# Deneigus_Servo.net
KiCad netlist of a schematic drawn in Altium Designer
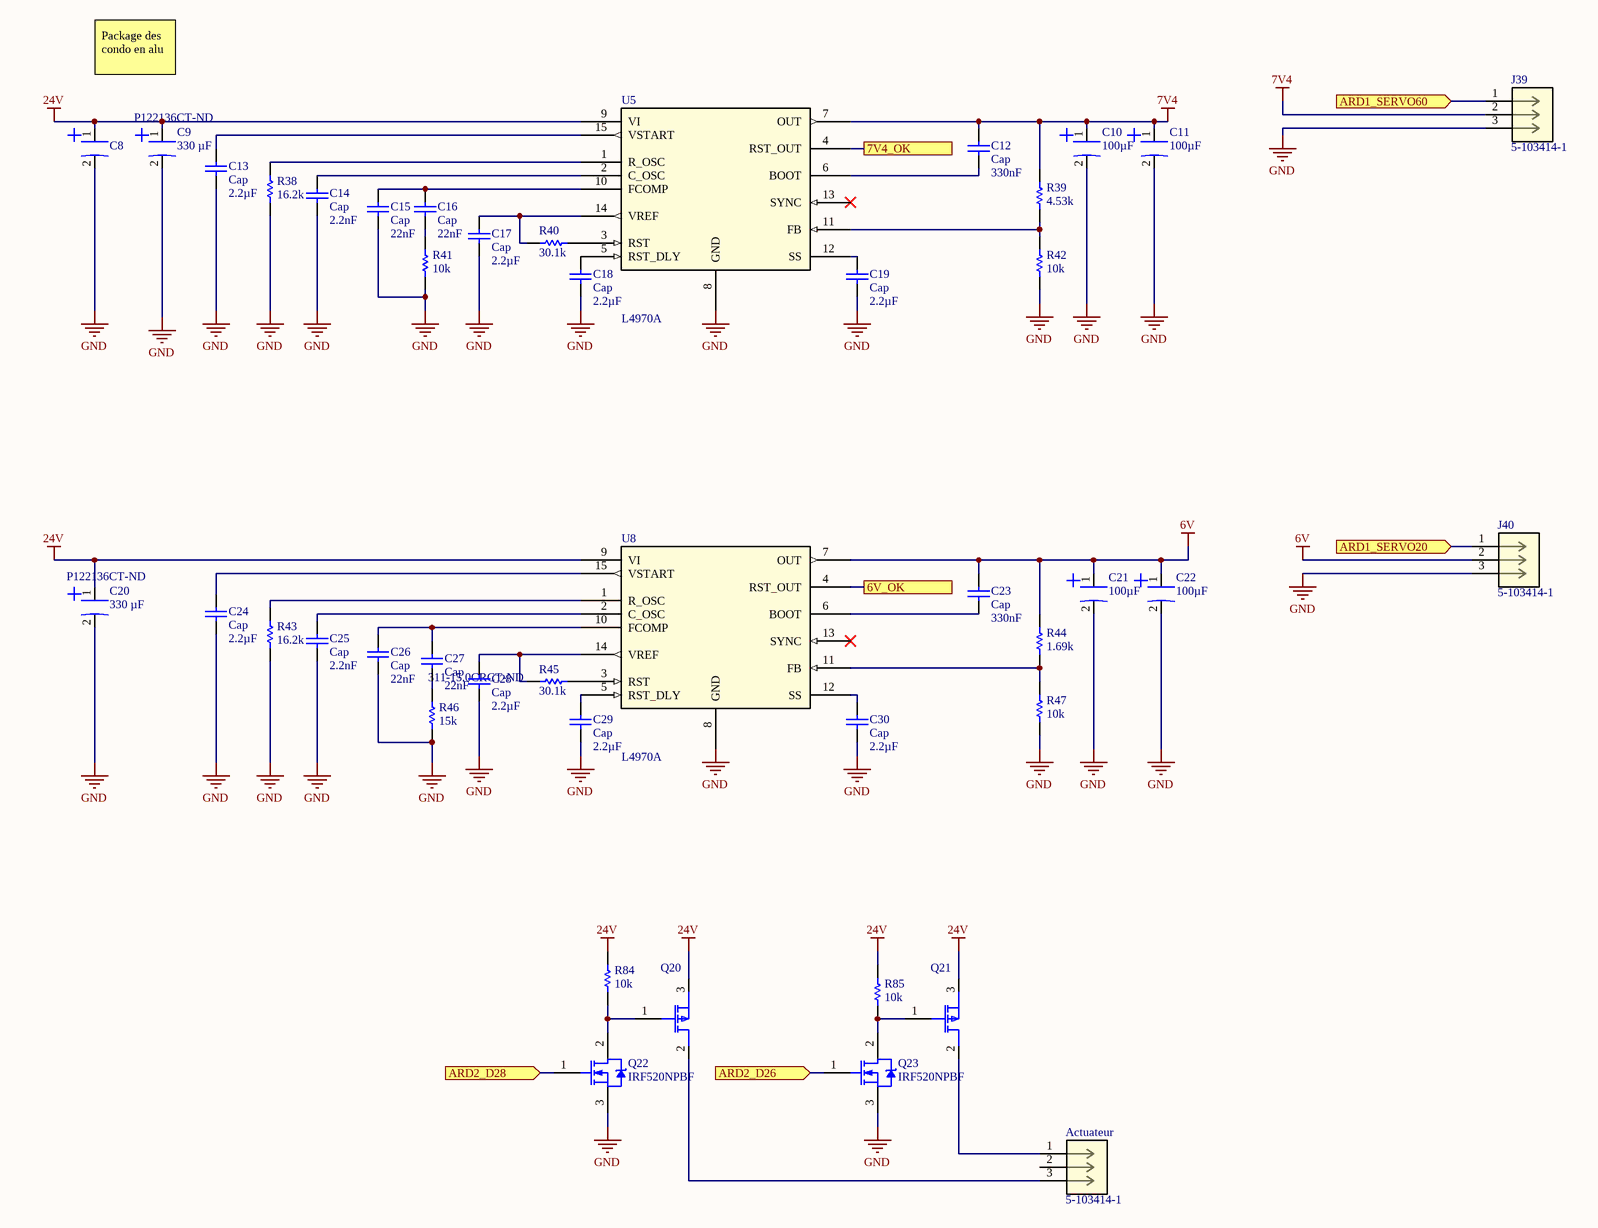
[diagram p0: Deneigus_Servo.SchDoc]

(export (version "E")
  (design (tool "Eeschema 10.0.6"))
  (components
    (comp (ref "Actuateur")
      (value "5-103414-1")
      (footprint "2021-04-13_19-21-58:CONN_5-103414-1_TYCO")
      (description "No Description Available")
      (fields (field (name "COPYRIGHT") "Copyright (C) 2016 Accelerated Designs. All rights reserved"))
      (libsource (lib "3pins") (part "5-103414-1"))
    )
    (comp (ref "C8")
      (value "CAP ALUM 3300UF 20% 50V SNAP")
      (footprint "3300 uF 50V Cap")
      (fields (field (name "VOLTAGE") "50V") (field (name "TOLERANCE") "20%"))
      (libsource (lib "S7CAS-APP1") (part "3300 µF 50V"))
    )
    (comp (ref "C9")
      (value "330 µF")
      (footprint "330uF (10.3x10.3mm)")
      (fields
        (field (name "MFG") "Würth Elektronik")
        (field (name "MFG PART NUMBER") "875105344006")
        (field (name "SUPPLIER PART NUMBER 1") "P122136CT-ND")
        (field (name "Comment") "CAP ALUM POLY 47UF 20% 16V SMD")
      )
      (libsource (lib "S7CAS-APP1") (part "47µF SMD"))
    )
    (comp (ref "C10")
      (value "100µF")
      (footprint "47uF")
      (fields
        (field (name "MFG") "Würth Elektronik")
        (field (name "MFG PART NUMBER") "875105344010")
        (field (name "Comment") "CAP ALUM POLY 47UF 20% 16V SMD")
      )
      (libsource (lib "S7CAS-APP1") (part "47µF SMD"))
    )
    (comp (ref "C11")
      (value "100µF")
      (footprint "47uF")
      (fields
        (field (name "MFG") "Würth Elektronik")
        (field (name "MFG PART NUMBER") "875105344010")
        (field (name "Comment") "CAP ALUM POLY 47UF 20% 16V SMD")
      )
      (libsource (lib "S7CAS-APP1") (part "47µF SMD"))
    )
    (comp (ref "C12")
      (value "Cap")
      (footprint "CAP_0805")
      (description "Capacitor")
      (fields (field (name "ALTIUM_VALUE") "330nF") (field (name "PUBLISHER") "Altium Limited"))
      (libsource (lib "Miscellaneous Devices") (part "Cap"))
    )
    (comp (ref "C13")
      (value "Cap")
      (footprint "CAP_0805")
      (description "Capacitor")
      (fields (field (name "ALTIUM_VALUE") "2.2µF") (field (name "PUBLISHER") "Altium Limited"))
      (libsource (lib "Miscellaneous Devices") (part "Cap"))
    )
    (comp (ref "C14")
      (value "Cap")
      (footprint "CAP_0805")
      (description "Capacitor")
      (fields (field (name "ALTIUM_VALUE") "2.2nF") (field (name "PUBLISHER") "Altium Limited"))
      (libsource (lib "Miscellaneous Devices") (part "Cap"))
    )
    (comp (ref "C15")
      (value "Cap")
      (footprint "RAD-0.3")
      (description "Capacitor")
      (fields (field (name "ALTIUM_VALUE") "22nF") (field (name "PUBLISHER") "Altium Limited"))
      (libsource (lib "Miscellaneous Devices") (part "Cap"))
    )
    (comp (ref "C16")
      (value "Cap")
      (footprint "RAD-0.3")
      (description "Capacitor")
      (fields (field (name "ALTIUM_VALUE") "22nF") (field (name "PUBLISHER") "Altium Limited"))
      (libsource (lib "Miscellaneous Devices") (part "Cap"))
    )
    (comp (ref "C17")
      (value "Cap")
      (footprint "CAP_0805")
      (description "Capacitor")
      (fields (field (name "ALTIUM_VALUE") "2.2µF") (field (name "PUBLISHER") "Altium Limited"))
      (libsource (lib "Miscellaneous Devices") (part "Cap"))
    )
    (comp (ref "C18")
      (value "Cap")
      (footprint "CAP_0805")
      (description "Capacitor")
      (fields (field (name "ALTIUM_VALUE") "2.2µF") (field (name "PUBLISHER") "Altium Limited"))
      (libsource (lib "Miscellaneous Devices") (part "Cap"))
    )
    (comp (ref "C19")
      (value "Cap")
      (footprint "CAP_0805")
      (description "Capacitor")
      (fields (field (name "ALTIUM_VALUE") "2.2µF") (field (name "PUBLISHER") "Altium Limited"))
      (libsource (lib "Miscellaneous Devices") (part "Cap"))
    )
    (comp (ref "C20")
      (value "330 µF")
      (footprint "330uF (10.3x10.3mm)")
      (fields
        (field (name "MFG") "Würth Elektronik")
        (field (name "MFG PART NUMBER") "875105344006")
        (field (name "SUPPLIER PART NUMBER 1") "P122136CT-ND")
        (field (name "Comment") "CAP ALUM POLY 47UF 20% 16V SMD")
      )
      (libsource (lib "S7CAS-APP1") (part "47µF SMD"))
    )
    (comp (ref "C21")
      (value "100µF")
      (footprint "47uF")
      (fields
        (field (name "MFG") "Würth Elektronik")
        (field (name "MFG PART NUMBER") "875105344010")
        (field (name "Comment") "CAP ALUM POLY 47UF 20% 16V SMD")
      )
      (libsource (lib "S7CAS-APP1") (part "47µF SMD"))
    )
    (comp (ref "C22")
      (value "100µF")
      (footprint "47uF")
      (fields
        (field (name "MFG") "Würth Elektronik")
        (field (name "MFG PART NUMBER") "875105344010")
        (field (name "Comment") "CAP ALUM POLY 47UF 20% 16V SMD")
      )
      (libsource (lib "S7CAS-APP1") (part "47µF SMD"))
    )
    (comp (ref "C23")
      (value "Cap")
      (footprint "CAP_0805")
      (description "Capacitor")
      (fields (field (name "ALTIUM_VALUE") "330nF") (field (name "PUBLISHER") "Altium Limited"))
      (libsource (lib "Miscellaneous Devices") (part "Cap"))
    )
    (comp (ref "C24")
      (value "Cap")
      (footprint "CAP_0805")
      (description "Capacitor")
      (fields (field (name "ALTIUM_VALUE") "2.2µF") (field (name "PUBLISHER") "Altium Limited"))
      (libsource (lib "Miscellaneous Devices") (part "Cap"))
    )
    (comp (ref "C25")
      (value "Cap")
      (footprint "CAP_0805")
      (description "Capacitor")
      (fields (field (name "ALTIUM_VALUE") "2.2nF") (field (name "PUBLISHER") "Altium Limited"))
      (libsource (lib "Miscellaneous Devices") (part "Cap"))
    )
    (comp (ref "C26")
      (value "Cap")
      (footprint "RAD-0.3")
      (description "Capacitor")
      (fields (field (name "ALTIUM_VALUE") "22nF") (field (name "PUBLISHER") "Altium Limited"))
      (libsource (lib "Miscellaneous Devices") (part "Cap"))
    )
    (comp (ref "C27")
      (value "Cap")
      (footprint "RAD-0.3")
      (description "Capacitor")
      (fields (field (name "ALTIUM_VALUE") "22nF") (field (name "PUBLISHER") "Altium Limited"))
      (libsource (lib "Miscellaneous Devices") (part "Cap"))
    )
    (comp (ref "C28")
      (value "Cap")
      (footprint "CAP_0805")
      (description "Capacitor")
      (fields (field (name "ALTIUM_VALUE") "2.2µF") (field (name "PUBLISHER") "Altium Limited"))
      (libsource (lib "Miscellaneous Devices") (part "Cap"))
    )
    (comp (ref "C29")
      (value "Cap")
      (footprint "CAP_0805")
      (description "Capacitor")
      (fields (field (name "ALTIUM_VALUE") "2.2µF") (field (name "PUBLISHER") "Altium Limited"))
      (libsource (lib "Miscellaneous Devices") (part "Cap"))
    )
    (comp (ref "C30")
      (value "Cap")
      (footprint "CAP_0805")
      (description "Capacitor")
      (fields (field (name "ALTIUM_VALUE") "2.2µF") (field (name "PUBLISHER") "Altium Limited"))
      (libsource (lib "Miscellaneous Devices") (part "Cap"))
    )
    (comp (ref "J39")
      (value "5-103414-1")
      (footprint "2021-04-13_19-21-58:CONN_5-103414-1_TYCO")
      (description "No Description Available")
      (fields (field (name "COPYRIGHT") "Copyright (C) 2016 Accelerated Designs. All rights reserved"))
      (libsource (lib "3pins") (part "5-103414-1"))
    )
    (comp (ref "J40")
      (value "5-103414-1")
      (footprint "2021-04-13_19-21-58:CONN_5-103414-1_TYCO")
      (description "No Description Available")
      (fields (field (name "COPYRIGHT") "Copyright (C) 2016 Accelerated Designs. All rights reserved"))
      (libsource (lib "3pins") (part "5-103414-1"))
    )
    (comp (ref "Q20")
      (value "MOSFET P-CH 55V 12A TO220AB")
      (footprint "IRF9Z24NPBF")
      (libsource (lib "S7CAS-APP1") (part "IRF9Z24NPBF"))
    )
    (comp (ref "Q21")
      (value "MOSFET P-CH 55V 12A TO220AB")
      (footprint "IRF9Z24NPBF")
      (libsource (lib "S7CAS-APP1") (part "IRF9Z24NPBF"))
    )
    (comp (ref "Q22")
      (value "IRF520NPBF")
      (footprint "INTR-TO-220AB-3")
      (description "HEXFET(R) Power MOSFET, 100 V, 9.7 A, 0.2 Ohm, -55 to 175 degC, 3-Pin FM (TO-220AB), RoHS, Tube")
      (fields (field (name "POWER") "48W") (field (name "MANUFACTURER") "International Rectifier"))
      (libsource (lib "Université de Sherbrooke") (part "NEMOS-GDS-3_B"))
    )
    (comp (ref "Q23")
      (value "IRF520NPBF")
      (footprint "INTR-TO-220AB-3")
      (description "HEXFET(R) Power MOSFET, 100 V, 9.7 A, 0.2 Ohm, -55 to 175 degC, 3-Pin FM (TO-220AB), RoHS, Tube")
      (fields (field (name "POWER") "48W") (field (name "MANUFACTURER") "International Rectifier"))
      (libsource (lib "Université de Sherbrooke") (part "NEMOS-GDS-3_B"))
    )
    (comp (ref "R38")
      (value "16.2k")
      (footprint "RES_0805")
      (description "Resistor")
      (fields (field (name "Comment") "Res1") (field (name "PUBLISHER") "Altium Limited"))
      (libsource (lib "Miscellaneous Devices") (part "Res1"))
    )
    (comp (ref "R39")
      (value "4.53k")
      (footprint "RES_0805")
      (description "Resistor")
      (fields (field (name "Comment") "Res1") (field (name "PUBLISHER") "Altium Limited"))
      (libsource (lib "Miscellaneous Devices") (part "Res1"))
    )
    (comp (ref "R40")
      (value "30.1k")
      (footprint "RES_0805")
      (description "Resistor")
      (fields (field (name "Comment") "Res1") (field (name "PUBLISHER") "Altium Limited"))
      (libsource (lib "Miscellaneous Devices") (part "Res1"))
    )
    (comp (ref "R41")
      (value "10k")
      (footprint "RES_0805")
      (description "Resistor")
      (fields (field (name "Comment") "Res1") (field (name "PUBLISHER") "Altium Limited"))
      (libsource (lib "Miscellaneous Devices") (part "Res1"))
    )
    (comp (ref "R42")
      (value "10k")
      (footprint "RES_0805")
      (description "Resistor")
      (fields (field (name "Comment") "Res1") (field (name "PUBLISHER") "Altium Limited"))
      (libsource (lib "Miscellaneous Devices") (part "Res1"))
    )
    (comp (ref "R43")
      (value "16.2k")
      (footprint "RES_0805")
      (description "Resistor")
      (fields (field (name "Comment") "Res1") (field (name "PUBLISHER") "Altium Limited"))
      (libsource (lib "Miscellaneous Devices") (part "Res1"))
    )
    (comp (ref "R44")
      (value "1.69k")
      (footprint "RES_0805")
      (description "Resistor")
      (fields (field (name "Comment") "Res1") (field (name "PUBLISHER") "Altium Limited"))
      (libsource (lib "Miscellaneous Devices") (part "Res1"))
    )
    (comp (ref "R45")
      (value "30.1k")
      (footprint "RES_0805")
      (description "Resistor")
      (fields (field (name "Comment") "Res1") (field (name "PUBLISHER") "Altium Limited"))
      (libsource (lib "Miscellaneous Devices") (part "Res1"))
    )
    (comp (ref "R46")
      (value "15k")
      (footprint "RES_0805")
      (description "Resistor")
      (fields
        (field (name "SUPPLIER PART NUMBER 1") "311-15.0CRCT-ND")
        (field (name "Comment") "Res1")
        (field (name "PUBLISHER") "Altium Limited")
      )
      (libsource (lib "Miscellaneous Devices") (part "Res1"))
    )
    (comp (ref "R47")
      (value "10k")
      (footprint "RES_0805")
      (description "Resistor")
      (fields (field (name "Comment") "Res1") (field (name "PUBLISHER") "Altium Limited"))
      (libsource (lib "Miscellaneous Devices") (part "Res1"))
    )
    (comp (ref "R84")
      (value "10k")
      (footprint "RES_0805")
      (description "Resistor")
      (fields (field (name "Comment") "Res1") (field (name "PUBLISHER") "Altium Limited"))
      (libsource (lib "Miscellaneous Devices") (part "Res1"))
    )
    (comp (ref "R85")
      (value "10k")
      (footprint "RES_0805")
      (description "Resistor")
      (fields (field (name "Comment") "Res1") (field (name "PUBLISHER") "Altium Limited"))
      (libsource (lib "Miscellaneous Devices") (part "Res1"))
    )
    (comp (ref "U5")
      (value "L4970A")
      (footprint "Multiwatt15_V_STM")
      (description "No Description Available")
      (fields (field (name "COPYRIGHT") "Copyright (C) 2018 Accelerated Designs. All rights reserved"))
      (libsource (lib "DCDC24_6") (part "L4970A"))
    )
    (comp (ref "U8")
      (value "L4970A")
      (footprint "Multiwatt15_V_STM")
      (description "No Description Available")
      (fields (field (name "COPYRIGHT") "Copyright (C) 2018 Accelerated Designs. All rights reserved"))
      (libsource (lib "DCDC24_6") (part "L4970A"))
    )
  )
  (nets
    (net (code "1") (name "/6V_OK") (class "Default")
      (node (ref "U8") (pin "4") (pinfunction "RST_OUT_4") (pintype "passive"))
    )
    (net (code "2") (name "/7V4_OK") (class "Default")
      (node (ref "U5") (pin "4") (pinfunction "RST_OUT_4") (pintype "passive"))
    )
    (net (code "3") (name "/ARD1_SERVO20") (class "Default")
      (node (ref "J40") (pin "1") (pinfunction "1_1") (pintype "passive"))
    )
    (net (code "4") (name "/ARD1_SERVO60") (class "Default")
      (node (ref "J39") (pin "1") (pinfunction "1_1") (pintype "passive"))
    )
    (net (code "5") (name "/ARD2_D26") (class "Default")
      (node (ref "Q23") (pin "1") (pinfunction "G_1") (pintype "passive"))
    )
    (net (code "6") (name "/ARD2_D28") (class "Default")
      (node (ref "Q22") (pin "1") (pinfunction "G_1") (pintype "passive"))
    )
    (net (code "7") (name "6V") (class "Default")
      (node (ref "C21") (pin "1") (pinfunction "1_1") (pintype "passive"))
      (node (ref "C22") (pin "1") (pinfunction "1_1") (pintype "passive"))
      (node (ref "C23") (pin "2") (pinfunction "2_2") (pintype "passive"))
      (node (ref "J40") (pin "2") (pinfunction "2_2") (pintype "passive"))
      (node (ref "R44") (pin "1") (pinfunction "1_1") (pintype "passive"))
      (node (ref "U8") (pin "7") (pinfunction "OUT_7") (pintype "output"))
    )
    (net (code "8") (name "7V4") (class "Default")
      (node (ref "C10") (pin "1") (pinfunction "1_1") (pintype "passive"))
      (node (ref "C11") (pin "1") (pinfunction "1_1") (pintype "passive"))
      (node (ref "C12") (pin "2") (pinfunction "2_2") (pintype "passive"))
      (node (ref "J39") (pin "2") (pinfunction "2_2") (pintype "passive"))
      (node (ref "R39") (pin "1") (pinfunction "1_1") (pintype "passive"))
      (node (ref "U5") (pin "7") (pinfunction "OUT_7") (pintype "output"))
    )
    (net (code "9") (name "24V") (class "Default")
      (node (ref "C20") (pin "1") (pinfunction "1_1") (pintype "passive"))
      (node (ref "C8") (pin "1") (pinfunction "1_1") (pintype "passive"))
      (node (ref "C9") (pin "1") (pinfunction "1_1") (pintype "passive"))
      (node (ref "Q20") (pin "3") (pinfunction "Source_3") (pintype "passive"))
      (node (ref "Q21") (pin "3") (pinfunction "Source_3") (pintype "passive"))
      (node (ref "R84") (pin "1") (pinfunction "1_1") (pintype "passive"))
      (node (ref "R85") (pin "1") (pinfunction "1_1") (pintype "passive"))
      (node (ref "U5") (pin "9") (pinfunction "VI_9") (pintype "power_in"))
      (node (ref "U8") (pin "9") (pinfunction "VI_9") (pintype "power_in"))
    )
    (net (code "10") (name "GND") (class "Default")
      (node (ref "C10") (pin "2") (pinfunction "2_2") (pintype "passive"))
      (node (ref "C11") (pin "2") (pinfunction "2_2") (pintype "passive"))
      (node (ref "C13") (pin "1") (pinfunction "1_1") (pintype "passive"))
      (node (ref "C14") (pin "1") (pinfunction "1_1") (pintype "passive"))
      (node (ref "C15") (pin "1") (pinfunction "1_1") (pintype "passive"))
      (node (ref "C17") (pin "1") (pinfunction "1_1") (pintype "passive"))
      (node (ref "C18") (pin "1") (pinfunction "1_1") (pintype "passive"))
      (node (ref "C19") (pin "1") (pinfunction "1_1") (pintype "passive"))
      (node (ref "C20") (pin "2") (pinfunction "2_2") (pintype "passive"))
      (node (ref "C21") (pin "2") (pinfunction "2_2") (pintype "passive"))
      (node (ref "C22") (pin "2") (pinfunction "2_2") (pintype "passive"))
      (node (ref "C24") (pin "1") (pinfunction "1_1") (pintype "passive"))
      (node (ref "C25") (pin "1") (pinfunction "1_1") (pintype "passive"))
      (node (ref "C26") (pin "1") (pinfunction "1_1") (pintype "passive"))
      (node (ref "C28") (pin "1") (pinfunction "1_1") (pintype "passive"))
      (node (ref "C29") (pin "1") (pinfunction "1_1") (pintype "passive"))
      (node (ref "C30") (pin "1") (pinfunction "1_1") (pintype "passive"))
      (node (ref "C8") (pin "2") (pinfunction "2_2") (pintype "passive"))
      (node (ref "C9") (pin "2") (pinfunction "2_2") (pintype "passive"))
      (node (ref "J39") (pin "3") (pinfunction "3_3") (pintype "passive"))
      (node (ref "J40") (pin "3") (pinfunction "3_3") (pintype "passive"))
      (node (ref "Q22") (pin "3") (pinfunction "S_3") (pintype "passive"))
      (node (ref "Q23") (pin "3") (pinfunction "S_3") (pintype "passive"))
      (node (ref "R38") (pin "2") (pinfunction "2_2") (pintype "passive"))
      (node (ref "R41") (pin "2") (pinfunction "2_2") (pintype "passive"))
      (node (ref "R42") (pin "2") (pinfunction "2_2") (pintype "passive"))
      (node (ref "R43") (pin "2") (pinfunction "2_2") (pintype "passive"))
      (node (ref "R46") (pin "2") (pinfunction "2_2") (pintype "passive"))
      (node (ref "R47") (pin "2") (pinfunction "2_2") (pintype "passive"))
      (node (ref "U5") (pin "8") (pinfunction "GND_8") (pintype "power_in"))
      (node (ref "U8") (pin "8") (pinfunction "GND_8") (pintype "power_in"))
    )
    (net (code "11") (name "Net-(C16-Pad1)") (class "Default")
      (node (ref "C16") (pin "1") (pinfunction "1_1") (pintype "passive"))
      (node (ref "R41") (pin "1") (pinfunction "1_1") (pintype "passive"))
    )
    (net (code "12") (name "Net-(C27-Pad1)") (class "Default")
      (node (ref "C27") (pin "1") (pinfunction "1_1") (pintype "passive"))
      (node (ref "R46") (pin "1") (pinfunction "1_1") (pintype "passive"))
    )
    (net (code "13") (name "Net-(Q20-Drain)") (class "Default")
      (node (ref "Actuateur") (pin "3") (pinfunction "3_3") (pintype "passive"))
      (node (ref "Q20") (pin "2") (pinfunction "Drain_2") (pintype "passive"))
    )
    (net (code "14") (name "Net-(Q20-Gate)") (class "Default")
      (node (ref "Q20") (pin "1") (pinfunction "Gate_1") (pintype "passive"))
      (node (ref "Q22") (pin "2") (pinfunction "D_2") (pintype "passive"))
      (node (ref "R84") (pin "2") (pinfunction "2_2") (pintype "passive"))
    )
    (net (code "15") (name "Net-(Q21-Drain)") (class "Default")
      (node (ref "Actuateur") (pin "1") (pinfunction "1_1") (pintype "passive"))
      (node (ref "Q21") (pin "2") (pinfunction "Drain_2") (pintype "passive"))
    )
    (net (code "16") (name "Net-(Q21-Gate)") (class "Default")
      (node (ref "Q21") (pin "1") (pinfunction "Gate_1") (pintype "passive"))
      (node (ref "Q23") (pin "2") (pinfunction "D_2") (pintype "passive"))
      (node (ref "R85") (pin "2") (pinfunction "2_2") (pintype "passive"))
    )
    (net (code "17") (name "Net-(U5-BOOT)") (class "Default")
      (node (ref "C12") (pin "1") (pinfunction "1_1") (pintype "passive"))
      (node (ref "U5") (pin "6") (pinfunction "BOOT_6") (pintype "passive"))
    )
    (net (code "18") (name "Net-(U5-C_OSC)") (class "Default")
      (node (ref "C14") (pin "2") (pinfunction "2_2") (pintype "passive"))
      (node (ref "U5") (pin "2") (pinfunction "C_OSC_2") (pintype "passive"))
    )
    (net (code "19") (name "Net-(U5-FB)") (class "Default")
      (node (ref "R39") (pin "2") (pinfunction "2_2") (pintype "passive"))
      (node (ref "R42") (pin "1") (pinfunction "1_1") (pintype "passive"))
      (node (ref "U5") (pin "11") (pinfunction "FB_11") (pintype "input"))
    )
    (net (code "20") (name "Net-(U5-FCOMP)") (class "Default")
      (node (ref "C15") (pin "2") (pinfunction "2_2") (pintype "passive"))
      (node (ref "C16") (pin "2") (pinfunction "2_2") (pintype "passive"))
      (node (ref "U5") (pin "10") (pinfunction "FCOMP_10") (pintype "passive"))
    )
    (net (code "21") (name "Net-(U5-RST)") (class "Default")
      (node (ref "R40") (pin "2") (pinfunction "2_2") (pintype "passive"))
      (node (ref "U5") (pin "3") (pinfunction "RST_3") (pintype "input"))
    )
    (net (code "22") (name "Net-(U5-RST_DLY)") (class "Default")
      (node (ref "C18") (pin "2") (pinfunction "2_2") (pintype "passive"))
      (node (ref "U5") (pin "5") (pinfunction "RST_DLY_5") (pintype "input"))
    )
    (net (code "23") (name "Net-(U5-R_OSC)") (class "Default")
      (node (ref "R38") (pin "1") (pinfunction "1_1") (pintype "passive"))
      (node (ref "U5") (pin "1") (pinfunction "R_OSC_1") (pintype "passive"))
    )
    (net (code "24") (name "Net-(U5-SS)") (class "Default")
      (node (ref "C19") (pin "2") (pinfunction "2_2") (pintype "passive"))
      (node (ref "U5") (pin "12") (pinfunction "SS_12") (pintype "passive"))
    )
    (net (code "25") (name "Net-(U5-VREF)") (class "Default")
      (node (ref "C17") (pin "2") (pinfunction "2_2") (pintype "passive"))
      (node (ref "R40") (pin "1") (pinfunction "1_1") (pintype "passive"))
      (node (ref "U5") (pin "14") (pinfunction "VREF_14") (pintype "output"))
    )
    (net (code "26") (name "Net-(U5-VSTART)") (class "Default")
      (node (ref "C13") (pin "2") (pinfunction "2_2") (pintype "passive"))
      (node (ref "U5") (pin "15") (pinfunction "VSTART_15") (pintype "output"))
    )
    (net (code "27") (name "Net-(U8-BOOT)") (class "Default")
      (node (ref "C23") (pin "1") (pinfunction "1_1") (pintype "passive"))
      (node (ref "U8") (pin "6") (pinfunction "BOOT_6") (pintype "passive"))
    )
    (net (code "28") (name "Net-(U8-C_OSC)") (class "Default")
      (node (ref "C25") (pin "2") (pinfunction "2_2") (pintype "passive"))
      (node (ref "U8") (pin "2") (pinfunction "C_OSC_2") (pintype "passive"))
    )
    (net (code "29") (name "Net-(U8-FB)") (class "Default")
      (node (ref "R44") (pin "2") (pinfunction "2_2") (pintype "passive"))
      (node (ref "R47") (pin "1") (pinfunction "1_1") (pintype "passive"))
      (node (ref "U8") (pin "11") (pinfunction "FB_11") (pintype "input"))
    )
    (net (code "30") (name "Net-(U8-FCOMP)") (class "Default")
      (node (ref "C26") (pin "2") (pinfunction "2_2") (pintype "passive"))
      (node (ref "C27") (pin "2") (pinfunction "2_2") (pintype "passive"))
      (node (ref "U8") (pin "10") (pinfunction "FCOMP_10") (pintype "passive"))
    )
    (net (code "31") (name "Net-(U8-RST)") (class "Default")
      (node (ref "R45") (pin "2") (pinfunction "2_2") (pintype "passive"))
      (node (ref "U8") (pin "3") (pinfunction "RST_3") (pintype "input"))
    )
    (net (code "32") (name "Net-(U8-RST_DLY)") (class "Default")
      (node (ref "C29") (pin "2") (pinfunction "2_2") (pintype "passive"))
      (node (ref "U8") (pin "5") (pinfunction "RST_DLY_5") (pintype "input"))
    )
    (net (code "33") (name "Net-(U8-R_OSC)") (class "Default")
      (node (ref "R43") (pin "1") (pinfunction "1_1") (pintype "passive"))
      (node (ref "U8") (pin "1") (pinfunction "R_OSC_1") (pintype "passive"))
    )
    (net (code "34") (name "Net-(U8-SS)") (class "Default")
      (node (ref "C30") (pin "2") (pinfunction "2_2") (pintype "passive"))
      (node (ref "U8") (pin "12") (pinfunction "SS_12") (pintype "passive"))
    )
    (net (code "35") (name "Net-(U8-VREF)") (class "Default")
      (node (ref "C28") (pin "2") (pinfunction "2_2") (pintype "passive"))
      (node (ref "R45") (pin "1") (pinfunction "1_1") (pintype "passive"))
      (node (ref "U8") (pin "14") (pinfunction "VREF_14") (pintype "output"))
    )
    (net (code "36") (name "Net-(U8-VSTART)") (class "Default")
      (node (ref "C24") (pin "2") (pinfunction "2_2") (pintype "passive"))
      (node (ref "U8") (pin "15") (pinfunction "VSTART_15") (pintype "output"))
    )
    (net (code "37") (name "unconnected-(Actuateur-Pad2)") (class "Default")
      (node (ref "Actuateur") (pin "2") (pinfunction "2_2") (pintype "passive"))
    )
    (net (code "38") (name "unconnected-(U5-SYNC-Pad13)") (class "Default")
      (node (ref "U5") (pin "13") (pinfunction "SYNC_13") (pintype "input+no_connect"))
    )
    (net (code "39") (name "unconnected-(U8-SYNC-Pad13)") (class "Default")
      (node (ref "U8") (pin "13") (pinfunction "SYNC_13") (pintype "input+no_connect"))
    )
  )
)
